# Sheet1.net
KiCad netlist of a schematic drawn in Altium Designer
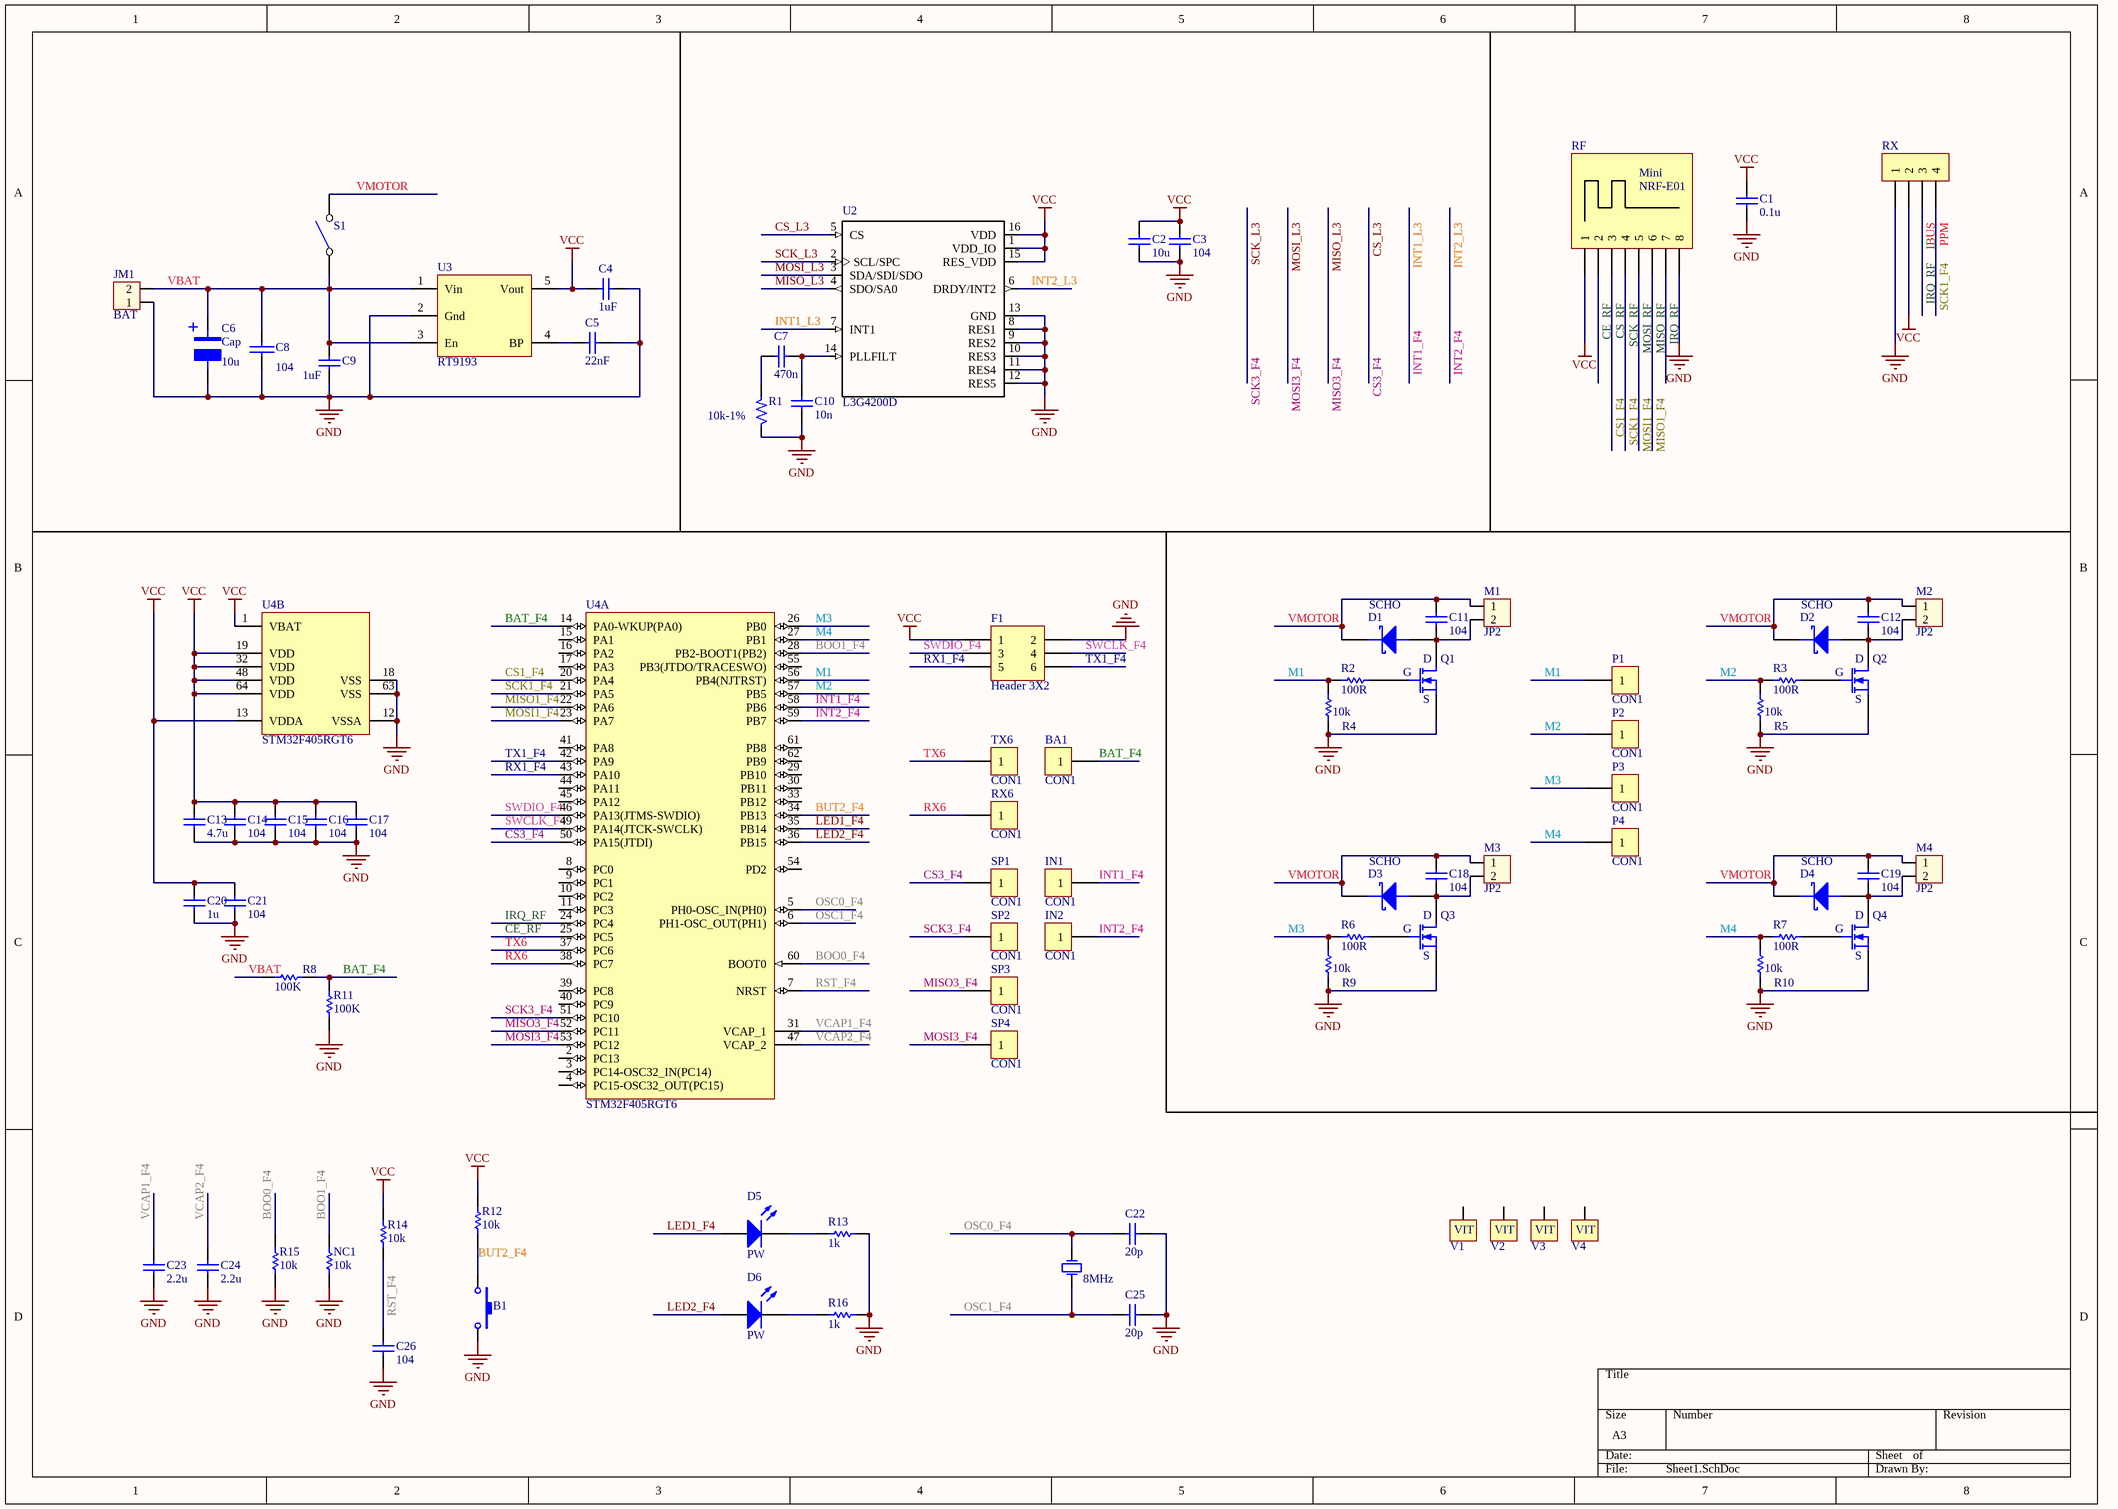
[diagram p0: Sheet1.SchDoc]

(export (version "E")
  (design (tool "Eeschema 10.0.6"))
  (components
    (comp (ref "B1")
      (value "SW-SMD")
      (footprint "SW-SMD")
      (description "Switch")
      (fields (field (name "PUBLISHER") "Altium Limited"))
      (libsource (lib "Cty1") (part "SW-SMD"))
    )
    (comp (ref "BA1")
      (value "CON1")
      (footprint "TEST-POINT")
      (description "Connector")
      (libsource (lib "") (part "CON1_1"))
    )
    (comp (ref "C1")
      (value "0.1u")
      (footprint "Cap-0603")
      (description "Capacitor")
      (fields (field (name "Comment") "Cap") (field (name "PUBLISHER") "Altium Limited"))
      (libsource (lib "Cty1") (part "Cap"))
    )
    (comp (ref "C2")
      (value "10u")
      (footprint "Cap-0603")
      (description "Capacitor")
      (fields (field (name "Comment") "Cap") (field (name "PUBLISHER") "Altium Limited"))
      (libsource (lib "Cty1") (part "Cap"))
    )
    (comp (ref "C3")
      (value "104")
      (footprint "Cap-0603")
      (description "Capacitor")
      (fields (field (name "Comment") "Cap") (field (name "PUBLISHER") "Altium Limited"))
      (libsource (lib "Cty1") (part "Cap"))
    )
    (comp (ref "C4")
      (value "1uF")
      (footprint "Cap-0603")
      (description "Capacitor")
      (fields (field (name "Comment") "Cap") (field (name "PUBLISHER") "Altium Limited"))
      (libsource (lib "Cty1") (part "Cap"))
    )
    (comp (ref "C5")
      (value "22nF")
      (footprint "Cap-0603")
      (description "Capacitor")
      (fields (field (name "Comment") "Cap") (field (name "PUBLISHER") "Altium Limited"))
      (libsource (lib "Cty1") (part "Cap"))
    )
    (comp (ref "C6")
      (value "Cap")
      (footprint "SMT_C_Tantalum_B")
      (fields (field (name "ALTIUM_VALUE") "10u"))
      (libsource (lib "Cty1") (part "Cap Pol"))
    )
    (comp (ref "C7")
      (value "470n")
      (footprint "Cap-0603")
      (description "Capacitor")
      (fields (field (name "Comment") "Cap") (field (name "PUBLISHER") "Altium Limited"))
      (libsource (lib "Cty1") (part "Cap"))
    )
    (comp (ref "C8")
      (value "104")
      (footprint "Cap-0603")
      (description "Capacitor")
      (fields (field (name "Comment") "Cap"))
      (libsource (lib "") (part "Cap_1"))
    )
    (comp (ref "C9")
      (value "1uF")
      (footprint "Cap-0603")
      (description "Capacitor")
      (fields (field (name "Comment") "Cap") (field (name "PUBLISHER") "Altium Limited"))
      (libsource (lib "Cty1") (part "Cap"))
    )
    (comp (ref "C10")
      (value "10n")
      (footprint "Cap-0603")
      (description "Capacitor")
      (fields (field (name "Comment") "Cap") (field (name "PUBLISHER") "Altium Limited"))
      (libsource (lib "Cty1") (part "Cap"))
    )
    (comp (ref "C11")
      (value "104")
      (footprint "Cap-0603")
      (description "Capacitor")
      (fields (field (name "Comment") "Cap") (field (name "PUBLISHER") "Altium Limited"))
      (libsource (lib "Cty1") (part "Cap"))
    )
    (comp (ref "C12")
      (value "104")
      (footprint "Cap-0603")
      (description "Capacitor")
      (fields (field (name "Comment") "Cap") (field (name "PUBLISHER") "Altium Limited"))
      (libsource (lib "Cty1") (part "Cap"))
    )
    (comp (ref "C13")
      (value "4.7u")
      (footprint "Cap-0603")
      (description "Capacitor")
      (fields (field (name "Comment") "Cap") (field (name "PUBLISHER") "Altium Limited"))
      (libsource (lib "Cty1") (part "Cap"))
    )
    (comp (ref "C14")
      (value "104")
      (footprint "Cap-0603")
      (description "Capacitor")
      (fields (field (name "Comment") "Cap") (field (name "PUBLISHER") "Altium Limited"))
      (libsource (lib "Cty1") (part "Cap"))
    )
    (comp (ref "C15")
      (value "104")
      (footprint "Cap-0603")
      (description "Capacitor")
      (fields (field (name "Comment") "Cap") (field (name "PUBLISHER") "Altium Limited"))
      (libsource (lib "Cty1") (part "Cap"))
    )
    (comp (ref "C16")
      (value "104")
      (footprint "Cap-0603")
      (description "Capacitor")
      (fields (field (name "Comment") "Cap") (field (name "PUBLISHER") "Altium Limited"))
      (libsource (lib "Cty1") (part "Cap"))
    )
    (comp (ref "C17")
      (value "104")
      (footprint "Cap-0603")
      (description "Capacitor")
      (fields (field (name "Comment") "Cap") (field (name "PUBLISHER") "Altium Limited"))
      (libsource (lib "Cty1") (part "Cap"))
    )
    (comp (ref "C18")
      (value "104")
      (footprint "Cap-0603")
      (description "Capacitor")
      (fields (field (name "Comment") "Cap") (field (name "PUBLISHER") "Altium Limited"))
      (libsource (lib "Cty1") (part "Cap"))
    )
    (comp (ref "C19")
      (value "104")
      (footprint "Cap-0603")
      (description "Capacitor")
      (fields (field (name "Comment") "Cap") (field (name "PUBLISHER") "Altium Limited"))
      (libsource (lib "Cty1") (part "Cap"))
    )
    (comp (ref "C20")
      (value "1u")
      (footprint "Cap-0603")
      (description "Capacitor")
      (fields (field (name "Comment") "Cap") (field (name "PUBLISHER") "Altium Limited"))
      (libsource (lib "Cty1") (part "Cap"))
    )
    (comp (ref "C21")
      (value "104")
      (footprint "Cap-0603")
      (description "Capacitor")
      (fields (field (name "Comment") "Cap") (field (name "PUBLISHER") "Altium Limited"))
      (libsource (lib "Cty1") (part "Cap"))
    )
    (comp (ref "C22")
      (value "20p")
      (footprint "Cap-0603")
      (description "Capacitor")
      (fields (field (name "Comment") "Cap") (field (name "PUBLISHER") "Altium Limited"))
      (libsource (lib "Cty1") (part "Cap"))
    )
    (comp (ref "C23")
      (value "2.2u")
      (footprint "Cap-0603")
      (description "Capacitor")
      (fields (field (name "Comment") "Cap") (field (name "PUBLISHER") "Altium Limited"))
      (libsource (lib "Cty1") (part "Cap"))
    )
    (comp (ref "C24")
      (value "2.2u")
      (footprint "Cap-0603")
      (description "Capacitor")
      (fields (field (name "Comment") "Cap") (field (name "PUBLISHER") "Altium Limited"))
      (libsource (lib "Cty1") (part "Cap"))
    )
    (comp (ref "C25")
      (value "20p")
      (footprint "Cap-0603")
      (description "Capacitor")
      (fields (field (name "Comment") "Cap") (field (name "PUBLISHER") "Altium Limited"))
      (libsource (lib "Cty1") (part "Cap"))
    )
    (comp (ref "C26")
      (value "104")
      (footprint "Cap-0603")
      (description "Capacitor")
      (fields (field (name "Comment") "Cap") (field (name "PUBLISHER") "Altium Limited"))
      (libsource (lib "Cty1") (part "Cap"))
    )
    (comp (ref "D1")
      (value "SCHO")
      (footprint "SMA")
      (description "Schottky Diode")
      (libsource (lib "Cty1") (part "DIODE SCHOTTKY"))
    )
    (comp (ref "D2")
      (value "SCHO")
      (footprint "SMA")
      (description "Schottky Diode")
      (libsource (lib "Cty1") (part "DIODE SCHOTTKY"))
    )
    (comp (ref "D3")
      (value "SCHO")
      (footprint "SMA")
      (description "Schottky Diode")
      (libsource (lib "Cty1") (part "DIODE SCHOTTKY"))
    )
    (comp (ref "D4")
      (value "SCHO")
      (footprint "SMA")
      (description "Schottky Diode")
      (libsource (lib "Cty1") (part "DIODE SCHOTTKY"))
    )
    (comp (ref "D5")
      (value "PW")
      (footprint "LED_SMD_0805_GREEN")
      (description "Typical INFRARED GaAs LED")
      (fields (field (name "PUBLISHER") "Altium Limited"))
      (libsource (lib "SCH_NHATBON") (part "LED"))
    )
    (comp (ref "D6")
      (value "PW")
      (footprint "LED_SMD_0805_RED")
      (description "Typical INFRARED GaAs LED")
      (fields (field (name "PUBLISHER") "Altium Limited"))
      (libsource (lib "SCH_NHATBON") (part "LED"))
    )
    (comp (ref "F1")
      (value "Header 3X2")
      (footprint "HDR2X3")
      (description "Header, 3-Pin, Dual row")
      (fields (field (name "PUBLISHER") "Altium Limited"))
      (libsource (lib "Cty1") (part "Header 3X2"))
    )
    (comp (ref "IN1")
      (value "CON1")
      (footprint "TEST-POINT")
      (description "Connector")
      (libsource (lib "") (part "CON1_1"))
    )
    (comp (ref "IN2")
      (value "CON1")
      (footprint "TEST-POINT")
      (description "Connector")
      (libsource (lib "") (part "CON1_1"))
    )
    (comp (ref "JM1")
      (value "BAT")
      (footprint "jp2h")
      (description "Connector 2")
      (libsource (lib "Cty1") (part "CON2"))
    )
    (comp (ref "M1")
      (value "JP2")
      (footprint "Con2 - 1.27MM")
      (description "Connector 2")
      (libsource (lib "") (part "CON2_1"))
    )
    (comp (ref "M2")
      (value "JP2")
      (footprint "Con2 - 1.27MM")
      (description "Connector 2")
      (libsource (lib "") (part "CON2_1"))
    )
    (comp (ref "M3")
      (value "JP2")
      (footprint "Con2 - 1.27MM")
      (description "Connector 2")
      (libsource (lib "") (part "CON2_1"))
    )
    (comp (ref "M4")
      (value "JP2")
      (footprint "Con2 - 1.27MM")
      (description "Connector 2")
      (libsource (lib "") (part "CON2_1"))
    )
    (comp (ref "NC1")
      (value "10k")
      (footprint "RES-SMD-0603")
      (description "Semiconductor Resistor")
      (fields (field (name "Comment") "Resistor") (field (name "PUBLISHER") "Altium Limited"))
      (libsource (lib "Cty1") (part "Resistor"))
    )
    (comp (ref "P1")
      (value "CON1")
      (footprint "TEST-POINT")
      (description "Connector")
      (libsource (lib "Cty1") (part "CON1"))
    )
    (comp (ref "P2")
      (value "CON1")
      (footprint "TEST-POINT")
      (description "Connector")
      (libsource (lib "Cty1") (part "CON1"))
    )
    (comp (ref "P3")
      (value "CON1")
      (footprint "TEST-POINT")
      (description "Connector")
      (libsource (lib "Cty1") (part "CON1"))
    )
    (comp (ref "P4")
      (value "CON1")
      (footprint "TEST-POINT")
      (description "Connector")
      (libsource (lib "Cty1") (part "CON1"))
    )
    (comp (ref "Q1")
      (value "Si2302DS")
      (footprint "SOT23-3")
      (description "N-Channel MOSFET")
      (fields (field (name "PUBLISHER") "Altium Limited"))
      (libsource (lib "Cty1") (part "Si2302DS"))
    )
    (comp (ref "Q2")
      (value "Si2302DS")
      (footprint "SOT23-3")
      (description "N-Channel MOSFET")
      (fields (field (name "PUBLISHER") "Altium Limited"))
      (libsource (lib "Cty1") (part "Si2302DS"))
    )
    (comp (ref "Q3")
      (value "Si2302DS")
      (footprint "SOT23-3")
      (description "N-Channel MOSFET")
      (fields (field (name "PUBLISHER") "Altium Limited"))
      (libsource (lib "Cty1") (part "Si2302DS"))
    )
    (comp (ref "Q4")
      (value "Si2302DS")
      (footprint "SOT23-3")
      (description "N-Channel MOSFET")
      (fields (field (name "PUBLISHER") "Altium Limited"))
      (libsource (lib "Cty1") (part "Si2302DS"))
    )
    (comp (ref "R1")
      (value "10k-1%")
      (footprint "RES-SMD-0603")
      (description "Resistor 1/4W")
      (libsource (lib "Cty1") (part "Res"))
    )
    (comp (ref "R2")
      (value "100R")
      (footprint "RES-SMD-0603")
      (description "Semiconductor Resistor")
      (fields (field (name "Comment") "Resistor") (field (name "PUBLISHER") "Altium Limited"))
      (libsource (lib "Cty1") (part "Resistor"))
    )
    (comp (ref "R3")
      (value "100R")
      (footprint "RES-SMD-0603")
      (description "Semiconductor Resistor")
      (fields (field (name "Comment") "Resistor") (field (name "PUBLISHER") "Altium Limited"))
      (libsource (lib "Cty1") (part "Resistor"))
    )
    (comp (ref "R4")
      (value "10k")
      (footprint "RES-SMD-0603")
      (description "Semiconductor Resistor")
      (fields (field (name "Comment") "Resistor") (field (name "PUBLISHER") "Altium Limited"))
      (libsource (lib "Cty1") (part "Resistor"))
    )
    (comp (ref "R5")
      (value "10k")
      (footprint "RES-SMD-0603")
      (description "Semiconductor Resistor")
      (fields (field (name "Comment") "Resistor") (field (name "PUBLISHER") "Altium Limited"))
      (libsource (lib "Cty1") (part "Resistor"))
    )
    (comp (ref "R6")
      (value "100R")
      (footprint "RES-SMD-0603")
      (description "Semiconductor Resistor")
      (fields (field (name "Comment") "Resistor") (field (name "PUBLISHER") "Altium Limited"))
      (libsource (lib "Cty1") (part "Resistor"))
    )
    (comp (ref "R7")
      (value "100R")
      (footprint "RES-SMD-0603")
      (description "Semiconductor Resistor")
      (fields (field (name "Comment") "Resistor") (field (name "PUBLISHER") "Altium Limited"))
      (libsource (lib "Cty1") (part "Resistor"))
    )
    (comp (ref "R8")
      (value "100K")
      (footprint "RES-SMD-0603")
      (description "Semiconductor Resistor")
      (fields (field (name "Comment") "Resistor") (field (name "PUBLISHER") "Altium Limited"))
      (libsource (lib "Cty1") (part "Resistor"))
    )
    (comp (ref "R9")
      (value "10k")
      (footprint "RES-SMD-0603")
      (description "Semiconductor Resistor")
      (fields (field (name "Comment") "Resistor") (field (name "PUBLISHER") "Altium Limited"))
      (libsource (lib "Cty1") (part "Resistor"))
    )
    (comp (ref "R10")
      (value "10k")
      (footprint "RES-SMD-0603")
      (description "Semiconductor Resistor")
      (fields (field (name "Comment") "Resistor") (field (name "PUBLISHER") "Altium Limited"))
      (libsource (lib "Cty1") (part "Resistor"))
    )
    (comp (ref "R11")
      (value "100K")
      (footprint "RES-SMD-0603")
      (description "Semiconductor Resistor")
      (fields (field (name "Comment") "Resistor") (field (name "PUBLISHER") "Altium Limited"))
      (libsource (lib "Cty1") (part "Resistor"))
    )
    (comp (ref "R12")
      (value "10k")
      (footprint "RES-SMD-0603")
      (description "Semiconductor Resistor")
      (fields (field (name "Comment") "Resistor") (field (name "PUBLISHER") "Altium Limited"))
      (libsource (lib "Cty1") (part "Resistor"))
    )
    (comp (ref "R13")
      (value "1k")
      (footprint "RES-SMD-0603")
      (description "Semiconductor Resistor")
      (fields (field (name "Comment") "Resistor") (field (name "PUBLISHER") "Altium Limited"))
      (libsource (lib "Cty1") (part "Resistor"))
    )
    (comp (ref "R14")
      (value "10k")
      (footprint "RES-SMD-0603")
      (description "Semiconductor Resistor")
      (fields (field (name "Comment") "Resistor") (field (name "PUBLISHER") "Altium Limited"))
      (libsource (lib "Cty1") (part "Resistor"))
    )
    (comp (ref "R15")
      (value "10k")
      (footprint "RES-SMD-0603")
      (description "Semiconductor Resistor")
      (fields (field (name "Comment") "Resistor") (field (name "PUBLISHER") "Altium Limited"))
      (libsource (lib "Cty1") (part "Resistor"))
    )
    (comp (ref "R16")
      (value "1k")
      (footprint "RES-SMD-0603")
      (description "Semiconductor Resistor")
      (fields (field (name "Comment") "Resistor") (field (name "PUBLISHER") "Altium Limited"))
      (libsource (lib "Cty1") (part "Resistor"))
    )
    (comp (ref "RF")
      (value "nRF24l01")
      (footprint "NRF-E01")
      (description "nRF24")
      (fields (field (name "PUBLISHER") "Altium Limited"))
      (libsource (lib "Cty1") (part "nRF24"))
    )
    (comp (ref "RX")
      (value "CON4")
      (footprint "SH4-1MM")
      (description "Connector")
      (libsource (lib "Cty1") (part "CON4"))
    )
    (comp (ref "RX6")
      (value "CON1")
      (footprint "TEST-POINT")
      (description "Connector")
      (libsource (lib "Cty1") (part "CON1"))
    )
    (comp (ref "S1") (value "SW SPST") (footprint "SW1-SMD") (libsource (lib "Cty1") (part "SW SPST")))
    (comp (ref "SP1")
      (value "CON1")
      (footprint "TEST-POINT")
      (description "Connector")
      (libsource (lib "Cty1") (part "CON1"))
    )
    (comp (ref "SP2")
      (value "CON1")
      (footprint "TEST-POINT")
      (description "Connector")
      (libsource (lib "Cty1") (part "CON1"))
    )
    (comp (ref "SP3")
      (value "CON1")
      (footprint "TEST-POINT")
      (description "Connector")
      (libsource (lib "Cty1") (part "CON1"))
    )
    (comp (ref "SP4")
      (value "CON1")
      (footprint "TEST-POINT")
      (description "Connector")
      (libsource (lib "Cty1") (part "CON1"))
    )
    (comp (ref "TX6")
      (value "CON1")
      (footprint "TEST-POINT")
      (description "Connector")
      (libsource (lib "Cty1") (part "CON1"))
    )
    (comp (ref "U2")
      (value "L3G4200D")
      (footprint "*PQFN65P400X400X110N")
      (description "Gyroscope X _Pitch_, Y _Roll_, Z _Yaw_ Â±250, 500, 2000 100Hz ~ 800Hz IÂ²C, SPI 16-LGA _4x4_")
      (fields (field (name "MF") "STMicroelectronics"))
      (libsource (lib "Cty1") (part "L3G4200D"))
    )
    (comp (ref "U3") (value "RT9193") (footprint "RT9193") (libsource (lib "Cty1") (part "RT9193")))
    (comp (ref "U4")
      (value "STM32F405RGT6")
      (footprint "STM-LQFP64_N")
      (fields (field (name "MANUFACTURER") "STMicroelectronics"))
      (libsource (lib "STMicroelectronics STM32 F4") (part "STM32F405RGT6"))
    )
    (comp (ref "V1")
      (value "1")
      (footprint "vit-2mm")
      (description "Oc Vit")
      (libsource (lib "Cty1") (part "VIT"))
    )
    (comp (ref "V2")
      (value "1")
      (footprint "vit-2mm")
      (description "Oc Vit")
      (libsource (lib "Cty1") (part "VIT"))
    )
    (comp (ref "V3")
      (value "1")
      (footprint "vit-2mm")
      (description "Oc Vit")
      (libsource (lib "Cty1") (part "VIT"))
    )
    (comp (ref "V4")
      (value "1")
      (footprint "vit-2mm")
      (description "Oc Vit")
      (libsource (lib "Cty1") (part "VIT"))
    )
    (comp (ref "Y1")
      (value "8MHz")
      (footprint "CRY_SMD_5032")
      (description "Crystal Oscillator")
      (fields (field (name "PUBLISHER") "Altium Limited"))
      (libsource (lib "Cty1") (part "Crystal"))
    )
  )
  (nets
    (net (code "1") (name "/BAT_F4") (class "Default")
      (node (ref "BA1") (pin "1") (pinfunction "1_1") (pintype "passive"))
      (node (ref "R11") (pin "2") (pinfunction "2_2") (pintype "passive"))
      (node (ref "R8") (pin "2") (pinfunction "2_2") (pintype "passive"))
      (node (ref "U4") (pin "14") (pinfunction "PA0-WKUP(PA0)_14") (pintype "bidirectional"))
    )
    (net (code "2") (name "/BOO0_F4") (class "Default")
      (node (ref "R15") (pin "2") (pinfunction "2_2") (pintype "passive"))
      (node (ref "U4") (pin "60") (pinfunction "BOOT0_60") (pintype "input"))
    )
    (net (code "3") (name "/BOO1_F4") (class "Default")
      (node (ref "NC1") (pin "2") (pinfunction "2_2") (pintype "passive"))
      (node (ref "U4") (pin "28") (pinfunction "PB2-BOOT1(PB2)_28") (pintype "bidirectional"))
    )
    (net (code "4") (name "/BUT2_F4") (class "Default")
      (node (ref "B1") (pin "1") (pinfunction "1_1") (pintype "passive"))
      (node (ref "R12") (pin "1") (pinfunction "1_1") (pintype "passive"))
      (node (ref "U4") (pin "34") (pinfunction "PB13_34") (pintype "bidirectional"))
    )
    (net (code "5") (name "/CE_RF") (class "Default")
      (node (ref "RF") (pin "2") (pinfunction "2_2") (pintype "passive"))
      (node (ref "U4") (pin "25") (pinfunction "PC5_25") (pintype "bidirectional"))
    )
    (net (code "6") (name "/CS1_F4") (class "Default")
      (node (ref "RF") (pin "3") (pinfunction "3_3") (pintype "passive"))
      (node (ref "U4") (pin "20") (pinfunction "PA4_20") (pintype "bidirectional"))
    )
    (net (code "7") (name "/CS3_F4") (class "Default")
      (node (ref "SP1") (pin "1") (pinfunction "1_1") (pintype "passive"))
      (node (ref "U2") (pin "5") (pinfunction "CS_5") (pintype "input"))
      (node (ref "U4") (pin "50") (pinfunction "PA15(JTDI)_50") (pintype "bidirectional"))
    )
    (net (code "8") (name "/IBUS") (class "Default")
      (node (ref "RF") (pin "7") (pinfunction "7_7") (pintype "passive"))
      (node (ref "RX") (pin "3") (pinfunction "3_3") (pintype "passive"))
      (node (ref "U4") (pin "24") (pinfunction "PC4_24") (pintype "bidirectional"))
    )
    (net (code "9") (name "/INT1_F4") (class "Default")
      (node (ref "IN1") (pin "1") (pinfunction "1_1") (pintype "passive"))
      (node (ref "U2") (pin "7") (pinfunction "INT1_7") (pintype "input"))
      (node (ref "U4") (pin "58") (pinfunction "PB6_58") (pintype "bidirectional"))
    )
    (net (code "10") (name "/INT2_F4") (class "Default")
      (node (ref "IN2") (pin "1") (pinfunction "1_1") (pintype "passive"))
      (node (ref "U2") (pin "6") (pinfunction "DRDY/INT2_6") (pintype "output"))
      (node (ref "U4") (pin "59") (pinfunction "PB7_59") (pintype "bidirectional"))
    )
    (net (code "11") (name "/LED1_F4") (class "Default")
      (node (ref "D5") (pin "1") (pinfunction "A_1") (pintype "passive"))
      (node (ref "U4") (pin "35") (pinfunction "PB14_35") (pintype "bidirectional"))
    )
    (net (code "12") (name "/LED2_F4") (class "Default")
      (node (ref "D6") (pin "1") (pinfunction "A_1") (pintype "passive"))
      (node (ref "U4") (pin "36") (pinfunction "PB15_36") (pintype "bidirectional"))
    )
    (net (code "13") (name "/M1") (class "Default")
      (node (ref "P1") (pin "1") (pinfunction "1_1") (pintype "passive"))
      (node (ref "R2") (pin "2") (pinfunction "2_2") (pintype "passive"))
      (node (ref "R4") (pin "1") (pinfunction "1_1") (pintype "passive"))
      (node (ref "U4") (pin "56") (pinfunction "PB4(NJTRST)_56") (pintype "bidirectional"))
    )
    (net (code "14") (name "/M2") (class "Default")
      (node (ref "P2") (pin "1") (pinfunction "1_1") (pintype "passive"))
      (node (ref "R3") (pin "2") (pinfunction "2_2") (pintype "passive"))
      (node (ref "R5") (pin "1") (pinfunction "1_1") (pintype "passive"))
      (node (ref "U4") (pin "57") (pinfunction "PB5_57") (pintype "bidirectional"))
    )
    (net (code "15") (name "/M3") (class "Default")
      (node (ref "P3") (pin "1") (pinfunction "1_1") (pintype "passive"))
      (node (ref "R6") (pin "2") (pinfunction "2_2") (pintype "passive"))
      (node (ref "R9") (pin "1") (pinfunction "1_1") (pintype "passive"))
      (node (ref "U4") (pin "26") (pinfunction "PB0_26") (pintype "bidirectional"))
    )
    (net (code "16") (name "/M4") (class "Default")
      (node (ref "P4") (pin "1") (pinfunction "1_1") (pintype "passive"))
      (node (ref "R10") (pin "1") (pinfunction "1_1") (pintype "passive"))
      (node (ref "R7") (pin "2") (pinfunction "2_2") (pintype "passive"))
      (node (ref "U4") (pin "27") (pinfunction "PB1_27") (pintype "bidirectional"))
    )
    (net (code "17") (name "/MISO1_F4") (class "Default")
      (node (ref "RF") (pin "6") (pinfunction "6_6") (pintype "passive"))
      (node (ref "U4") (pin "22") (pinfunction "PA6_22") (pintype "bidirectional"))
    )
    (net (code "18") (name "/MISO3_F4") (class "Default")
      (node (ref "SP3") (pin "1") (pinfunction "1_1") (pintype "passive"))
      (node (ref "U2") (pin "4") (pinfunction "SDO/SA0_4") (pintype "output"))
      (node (ref "U4") (pin "52") (pinfunction "PC11_52") (pintype "bidirectional"))
    )
    (net (code "19") (name "/MOSI1_F4") (class "Default")
      (node (ref "RF") (pin "5") (pinfunction "5_5") (pintype "passive"))
      (node (ref "U4") (pin "23") (pinfunction "PA7_23") (pintype "bidirectional"))
    )
    (net (code "20") (name "/MOSI3_F4") (class "Default")
      (node (ref "SP4") (pin "1") (pinfunction "1_1") (pintype "passive"))
      (node (ref "U2") (pin "3") (pinfunction "SDA/SDI/SDO_3") (pintype "bidirectional"))
      (node (ref "U4") (pin "53") (pinfunction "PC12_53") (pintype "bidirectional"))
    )
    (net (code "21") (name "/OSC0_F4") (class "Default")
      (node (ref "C22") (pin "2") (pinfunction "2_2") (pintype "passive"))
      (node (ref "U4") (pin "5") (pinfunction "PH0-OSC_IN(PH0)_5") (pintype "bidirectional"))
      (node (ref "Y1") (pin "2") (pinfunction "OSC2_2") (pintype "passive"))
    )
    (net (code "22") (name "/OSC1_F4") (class "Default")
      (node (ref "C25") (pin "2") (pinfunction "2_2") (pintype "passive"))
      (node (ref "U4") (pin "6") (pinfunction "PH1-OSC_OUT(PH1)_6") (pintype "bidirectional"))
      (node (ref "Y1") (pin "1") (pinfunction "OSC1_1") (pintype "passive"))
    )
    (net (code "23") (name "/PPM") (class "Default")
      (node (ref "RF") (pin "4") (pinfunction "4_4") (pintype "passive"))
      (node (ref "RX") (pin "4") (pinfunction "4_4") (pintype "passive"))
      (node (ref "U4") (pin "21") (pinfunction "PA5_21") (pintype "bidirectional"))
    )
    (net (code "24") (name "/RST_F4") (class "Default")
      (node (ref "C26") (pin "2") (pinfunction "2_2") (pintype "passive"))
      (node (ref "R14") (pin "1") (pinfunction "1_1") (pintype "passive"))
      (node (ref "U4") (pin "7") (pinfunction "NRST_7") (pintype "bidirectional"))
    )
    (net (code "25") (name "/RX1_F4") (class "Default")
      (node (ref "F1") (pin "5") (pinfunction "5_5") (pintype "passive"))
      (node (ref "U4") (pin "43") (pinfunction "PA10_43") (pintype "bidirectional"))
    )
    (net (code "26") (name "/RX6") (class "Default")
      (node (ref "RX6") (pin "1") (pinfunction "1_1") (pintype "passive"))
      (node (ref "U4") (pin "38") (pinfunction "PC7_38") (pintype "bidirectional"))
    )
    (net (code "27") (name "/SCK3_F4") (class "Default")
      (node (ref "SP2") (pin "1") (pinfunction "1_1") (pintype "passive"))
      (node (ref "U2") (pin "2") (pinfunction "SCL/SPC_2") (pintype "input"))
      (node (ref "U4") (pin "51") (pinfunction "PC10_51") (pintype "bidirectional"))
    )
    (net (code "28") (name "/SWCLK_F4") (class "Default")
      (node (ref "F1") (pin "4") (pinfunction "4_4") (pintype "passive"))
      (node (ref "U4") (pin "49") (pinfunction "PA14(JTCK-SWCLK)_49") (pintype "bidirectional"))
    )
    (net (code "29") (name "/SWDIO_F4") (class "Default")
      (node (ref "F1") (pin "3") (pinfunction "3_3") (pintype "passive"))
      (node (ref "U4") (pin "46") (pinfunction "PA13(JTMS-SWDIO)_46") (pintype "bidirectional"))
    )
    (net (code "30") (name "/TX1_F4") (class "Default")
      (node (ref "F1") (pin "6") (pinfunction "6_6") (pintype "passive"))
      (node (ref "U4") (pin "42") (pinfunction "PA9_42") (pintype "bidirectional"))
    )
    (net (code "31") (name "/TX6") (class "Default")
      (node (ref "TX6") (pin "1") (pinfunction "1_1") (pintype "passive"))
      (node (ref "U4") (pin "37") (pinfunction "PC6_37") (pintype "bidirectional"))
    )
    (net (code "32") (name "/VBAT") (class "Default")
      (node (ref "C6") (pin "1") (pinfunction "1_1") (pintype "passive"))
      (node (ref "C8") (pin "1") (pinfunction "1_1") (pintype "passive"))
      (node (ref "C9") (pin "1") (pinfunction "1_1") (pintype "passive"))
      (node (ref "JM1") (pin "2") (pinfunction "2_2") (pintype "passive"))
      (node (ref "R8") (pin "1") (pinfunction "1_1") (pintype "passive"))
      (node (ref "S1") (pin "1") (pinfunction "COMMON_1") (pintype "passive"))
      (node (ref "U3") (pin "1") (pinfunction "Vin_1") (pintype "passive"))
      (node (ref "U3") (pin "3") (pinfunction "En_3") (pintype "passive"))
    )
    (net (code "33") (name "/VCAP1_F4") (class "Default")
      (node (ref "C23") (pin "2") (pinfunction "2_2") (pintype "passive"))
      (node (ref "U4") (pin "31") (pinfunction "VCAP_1_31") (pintype "power_in"))
    )
    (net (code "34") (name "/VCAP2_F4") (class "Default")
      (node (ref "C24") (pin "2") (pinfunction "2_2") (pintype "passive"))
      (node (ref "U4") (pin "47") (pinfunction "VCAP_2_47") (pintype "power_in"))
    )
    (net (code "35") (name "/VMOTOR") (class "Default")
      (node (ref "C11") (pin "2") (pinfunction "2_2") (pintype "passive"))
      (node (ref "C12") (pin "2") (pinfunction "2_2") (pintype "passive"))
      (node (ref "C18") (pin "2") (pinfunction "2_2") (pintype "passive"))
      (node (ref "C19") (pin "2") (pinfunction "2_2") (pintype "passive"))
      (node (ref "D1") (pin "2") (pinfunction "K_2") (pintype "passive"))
      (node (ref "D2") (pin "2") (pinfunction "K_2") (pintype "passive"))
      (node (ref "D3") (pin "2") (pinfunction "K_2") (pintype "passive"))
      (node (ref "D4") (pin "2") (pinfunction "K_2") (pintype "passive"))
      (node (ref "M1") (pin "1") (pinfunction "1_1") (pintype "passive"))
      (node (ref "M2") (pin "1") (pinfunction "1_1") (pintype "passive"))
      (node (ref "M3") (pin "1") (pinfunction "1_1") (pintype "passive"))
      (node (ref "M4") (pin "1") (pinfunction "1_1") (pintype "passive"))
      (node (ref "S1") (pin "2") (pinfunction "NO_2") (pintype "passive"))
    )
    (net (code "36") (name "GND") (class "Default")
      (node (ref "B1") (pin "2") (pinfunction "2_2") (pintype "passive"))
      (node (ref "C1") (pin "1") (pinfunction "1_1") (pintype "passive"))
      (node (ref "C10") (pin "1") (pinfunction "1_1") (pintype "passive"))
      (node (ref "C13") (pin "1") (pinfunction "1_1") (pintype "passive"))
      (node (ref "C14") (pin "1") (pinfunction "1_1") (pintype "passive"))
      (node (ref "C15") (pin "1") (pinfunction "1_1") (pintype "passive"))
      (node (ref "C16") (pin "1") (pinfunction "1_1") (pintype "passive"))
      (node (ref "C17") (pin "1") (pinfunction "1_1") (pintype "passive"))
      (node (ref "C2") (pin "1") (pinfunction "1_1") (pintype "passive"))
      (node (ref "C20") (pin "1") (pinfunction "1_1") (pintype "passive"))
      (node (ref "C21") (pin "1") (pinfunction "1_1") (pintype "passive"))
      (node (ref "C22") (pin "1") (pinfunction "1_1") (pintype "passive"))
      (node (ref "C23") (pin "1") (pinfunction "1_1") (pintype "passive"))
      (node (ref "C24") (pin "1") (pinfunction "1_1") (pintype "passive"))
      (node (ref "C25") (pin "1") (pinfunction "1_1") (pintype "passive"))
      (node (ref "C26") (pin "1") (pinfunction "1_1") (pintype "passive"))
      (node (ref "C3") (pin "1") (pinfunction "1_1") (pintype "passive"))
      (node (ref "C4") (pin "1") (pinfunction "1_1") (pintype "passive"))
      (node (ref "C5") (pin "1") (pinfunction "1_1") (pintype "passive"))
      (node (ref "C6") (pin "2") (pinfunction "2_2") (pintype "passive"))
      (node (ref "C8") (pin "2") (pinfunction "2_2") (pintype "passive"))
      (node (ref "C9") (pin "2") (pinfunction "2_2") (pintype "passive"))
      (node (ref "F1") (pin "2") (pinfunction "2_2") (pintype "passive"))
      (node (ref "JM1") (pin "1") (pinfunction "1_1") (pintype "passive"))
      (node (ref "NC1") (pin "1") (pinfunction "1_1") (pintype "passive"))
      (node (ref "Q1") (pin "2") (pinfunction "S_2") (pintype "passive"))
      (node (ref "Q2") (pin "2") (pinfunction "S_2") (pintype "passive"))
      (node (ref "Q3") (pin "2") (pinfunction "S_2") (pintype "passive"))
      (node (ref "Q4") (pin "2") (pinfunction "S_2") (pintype "passive"))
      (node (ref "R1") (pin "1") (pinfunction "1_1") (pintype "passive"))
      (node (ref "R10") (pin "2") (pinfunction "2_2") (pintype "passive"))
      (node (ref "R11") (pin "1") (pinfunction "1_1") (pintype "passive"))
      (node (ref "R13") (pin "2") (pinfunction "2_2") (pintype "passive"))
      (node (ref "R15") (pin "1") (pinfunction "1_1") (pintype "passive"))
      (node (ref "R16") (pin "2") (pinfunction "2_2") (pintype "passive"))
      (node (ref "R4") (pin "2") (pinfunction "2_2") (pintype "passive"))
      (node (ref "R5") (pin "2") (pinfunction "2_2") (pintype "passive"))
      (node (ref "R9") (pin "2") (pinfunction "2_2") (pintype "passive"))
      (node (ref "RF") (pin "8") (pinfunction "8_8") (pintype "passive"))
      (node (ref "RX") (pin "1") (pinfunction "1_1") (pintype "passive"))
      (node (ref "U2") (pin "10") (pinfunction "RES3_10") (pintype "power_in"))
      (node (ref "U2") (pin "11") (pinfunction "RES4_11") (pintype "power_in"))
      (node (ref "U2") (pin "12") (pinfunction "RES5_12") (pintype "power_in"))
      (node (ref "U2") (pin "13") (pinfunction "GND_13") (pintype "power_in"))
      (node (ref "U2") (pin "8") (pinfunction "RES1_8") (pintype "power_in"))
      (node (ref "U2") (pin "9") (pinfunction "RES2_9") (pintype "power_in"))
      (node (ref "U3") (pin "2") (pinfunction "Gnd_2") (pintype "passive"))
      (node (ref "U4") (pin "12") (pinfunction "VSSA_12") (pintype "power_in"))
      (node (ref "U4") (pin "18") (pinfunction "VSS_18") (pintype "power_in"))
      (node (ref "U4") (pin "63") (pinfunction "VSS_63") (pintype "power_in"))
    )
    (net (code "37") (name "Net-(C7-Pad1)") (class "Default")
      (node (ref "C7") (pin "1") (pinfunction "1_1") (pintype "passive"))
      (node (ref "R1") (pin "2") (pinfunction "2_2") (pintype "passive"))
    )
    (net (code "38") (name "Net-(D1-A)") (class "Default")
      (node (ref "C11") (pin "1") (pinfunction "1_1") (pintype "passive"))
      (node (ref "D1") (pin "1") (pinfunction "A_1") (pintype "passive"))
      (node (ref "M1") (pin "2") (pinfunction "2_2") (pintype "passive"))
      (node (ref "Q1") (pin "3") (pinfunction "D_3") (pintype "passive"))
    )
    (net (code "39") (name "Net-(D2-A)") (class "Default")
      (node (ref "C12") (pin "1") (pinfunction "1_1") (pintype "passive"))
      (node (ref "D2") (pin "1") (pinfunction "A_1") (pintype "passive"))
      (node (ref "M2") (pin "2") (pinfunction "2_2") (pintype "passive"))
      (node (ref "Q2") (pin "3") (pinfunction "D_3") (pintype "passive"))
    )
    (net (code "40") (name "Net-(D3-A)") (class "Default")
      (node (ref "C18") (pin "1") (pinfunction "1_1") (pintype "passive"))
      (node (ref "D3") (pin "1") (pinfunction "A_1") (pintype "passive"))
      (node (ref "M3") (pin "2") (pinfunction "2_2") (pintype "passive"))
      (node (ref "Q3") (pin "3") (pinfunction "D_3") (pintype "passive"))
    )
    (net (code "41") (name "Net-(D4-A)") (class "Default")
      (node (ref "C19") (pin "1") (pinfunction "1_1") (pintype "passive"))
      (node (ref "D4") (pin "1") (pinfunction "A_1") (pintype "passive"))
      (node (ref "M4") (pin "2") (pinfunction "2_2") (pintype "passive"))
      (node (ref "Q4") (pin "3") (pinfunction "D_3") (pintype "passive"))
    )
    (net (code "42") (name "Net-(D5-K)") (class "Default")
      (node (ref "D5") (pin "2") (pinfunction "K_2") (pintype "passive"))
      (node (ref "R13") (pin "1") (pinfunction "1_1") (pintype "passive"))
    )
    (net (code "43") (name "Net-(D6-K)") (class "Default")
      (node (ref "D6") (pin "2") (pinfunction "K_2") (pintype "passive"))
      (node (ref "R16") (pin "1") (pinfunction "1_1") (pintype "passive"))
    )
    (net (code "44") (name "Net-(Q1-G)") (class "Default")
      (node (ref "Q1") (pin "1") (pinfunction "G_1") (pintype "passive"))
      (node (ref "R2") (pin "1") (pinfunction "1_1") (pintype "passive"))
    )
    (net (code "45") (name "Net-(Q2-G)") (class "Default")
      (node (ref "Q2") (pin "1") (pinfunction "G_1") (pintype "passive"))
      (node (ref "R3") (pin "1") (pinfunction "1_1") (pintype "passive"))
    )
    (net (code "46") (name "Net-(Q3-G)") (class "Default")
      (node (ref "Q3") (pin "1") (pinfunction "G_1") (pintype "passive"))
      (node (ref "R6") (pin "1") (pinfunction "1_1") (pintype "passive"))
    )
    (net (code "47") (name "Net-(Q4-G)") (class "Default")
      (node (ref "Q4") (pin "1") (pinfunction "G_1") (pintype "passive"))
      (node (ref "R7") (pin "1") (pinfunction "1_1") (pintype "passive"))
    )
    (net (code "48") (name "Net-(U2-PLLFILT)") (class "Default")
      (node (ref "C10") (pin "2") (pinfunction "2_2") (pintype "passive"))
      (node (ref "C7") (pin "2") (pinfunction "2_2") (pintype "passive"))
      (node (ref "U2") (pin "14") (pinfunction "PLLFILT_14") (pintype "input"))
    )
    (net (code "49") (name "Net-(U3-BP)") (class "Default")
      (node (ref "C5") (pin "2") (pinfunction "2_2") (pintype "passive"))
      (node (ref "U3") (pin "4") (pinfunction "BP_4") (pintype "passive"))
    )
    (net (code "50") (name "VCC") (class "Default")
      (node (ref "C1") (pin "2") (pinfunction "2_2") (pintype "passive"))
      (node (ref "C13") (pin "2") (pinfunction "2_2") (pintype "passive"))
      (node (ref "C14") (pin "2") (pinfunction "2_2") (pintype "passive"))
      (node (ref "C15") (pin "2") (pinfunction "2_2") (pintype "passive"))
      (node (ref "C16") (pin "2") (pinfunction "2_2") (pintype "passive"))
      (node (ref "C17") (pin "2") (pinfunction "2_2") (pintype "passive"))
      (node (ref "C2") (pin "2") (pinfunction "2_2") (pintype "passive"))
      (node (ref "C20") (pin "2") (pinfunction "2_2") (pintype "passive"))
      (node (ref "C21") (pin "2") (pinfunction "2_2") (pintype "passive"))
      (node (ref "C3") (pin "2") (pinfunction "2_2") (pintype "passive"))
      (node (ref "C4") (pin "2") (pinfunction "2_2") (pintype "passive"))
      (node (ref "F1") (pin "1") (pinfunction "1_1") (pintype "passive"))
      (node (ref "R12") (pin "2") (pinfunction "2_2") (pintype "passive"))
      (node (ref "R14") (pin "2") (pinfunction "2_2") (pintype "passive"))
      (node (ref "RF") (pin "1") (pinfunction "1_1") (pintype "passive"))
      (node (ref "RX") (pin "2") (pinfunction "2_2") (pintype "passive"))
      (node (ref "U2") (pin "1") (pinfunction "VDD_IO_1") (pintype "power_in"))
      (node (ref "U2") (pin "15") (pinfunction "RES_VDD_15") (pintype "power_in"))
      (node (ref "U2") (pin "16") (pinfunction "VDD_16") (pintype "power_in"))
      (node (ref "U3") (pin "5") (pinfunction "Vout_5") (pintype "passive"))
      (node (ref "U4") (pin "1") (pinfunction "VBAT_1") (pintype "power_in"))
      (node (ref "U4") (pin "13") (pinfunction "VDDA_13") (pintype "power_in"))
      (node (ref "U4") (pin "19") (pinfunction "VDD_19") (pintype "power_in"))
      (node (ref "U4") (pin "32") (pinfunction "VDD_32") (pintype "power_in"))
      (node (ref "U4") (pin "48") (pinfunction "VDD_48") (pintype "power_in"))
      (node (ref "U4") (pin "64") (pinfunction "VDD_64") (pintype "power_in"))
    )
    (net (code "51") (name "unconnected-(U4A-PA1-Pad15)") (class "Default")
      (node (ref "U4") (pin "15") (pinfunction "PA1_15") (pintype "bidirectional"))
    )
    (net (code "52") (name "unconnected-(U4A-PA2-Pad16)") (class "Default")
      (node (ref "U4") (pin "16") (pinfunction "PA2_16") (pintype "bidirectional"))
    )
    (net (code "53") (name "unconnected-(U4A-PA3-Pad17)") (class "Default")
      (node (ref "U4") (pin "17") (pinfunction "PA3_17") (pintype "bidirectional"))
    )
    (net (code "54") (name "unconnected-(U4A-PA8-Pad41)") (class "Default")
      (node (ref "U4") (pin "41") (pinfunction "PA8_41") (pintype "bidirectional"))
    )
    (net (code "55") (name "unconnected-(U4A-PA11-Pad44)") (class "Default")
      (node (ref "U4") (pin "44") (pinfunction "PA11_44") (pintype "bidirectional"))
    )
    (net (code "56") (name "unconnected-(U4A-PA12-Pad45)") (class "Default")
      (node (ref "U4") (pin "45") (pinfunction "PA12_45") (pintype "bidirectional"))
    )
    (net (code "57") (name "unconnected-(U4A-PB3(JTDO{slash}TRACESWO)-Pad55)") (class "Default")
      (node (ref "U4") (pin "55") (pinfunction "PB3(JTDO/TRACESWO)_55") (pintype "bidirectional"))
    )
    (net (code "58") (name "unconnected-(U4A-PB8-Pad61)") (class "Default")
      (node (ref "U4") (pin "61") (pinfunction "PB8_61") (pintype "bidirectional"))
    )
    (net (code "59") (name "unconnected-(U4A-PB9-Pad62)") (class "Default")
      (node (ref "U4") (pin "62") (pinfunction "PB9_62") (pintype "bidirectional"))
    )
    (net (code "60") (name "unconnected-(U4A-PB10-Pad29)") (class "Default")
      (node (ref "U4") (pin "29") (pinfunction "PB10_29") (pintype "bidirectional"))
    )
    (net (code "61") (name "unconnected-(U4A-PB11-Pad30)") (class "Default")
      (node (ref "U4") (pin "30") (pinfunction "PB11_30") (pintype "bidirectional"))
    )
    (net (code "62") (name "unconnected-(U4A-PB12-Pad33)") (class "Default")
      (node (ref "U4") (pin "33") (pinfunction "PB12_33") (pintype "bidirectional"))
    )
    (net (code "63") (name "unconnected-(U4A-PC0-Pad8)") (class "Default")
      (node (ref "U4") (pin "8") (pinfunction "PC0_8") (pintype "bidirectional"))
    )
    (net (code "64") (name "unconnected-(U4A-PC1-Pad9)") (class "Default")
      (node (ref "U4") (pin "9") (pinfunction "PC1_9") (pintype "bidirectional"))
    )
    (net (code "65") (name "unconnected-(U4A-PC2-Pad10)") (class "Default")
      (node (ref "U4") (pin "10") (pinfunction "PC2_10") (pintype "bidirectional"))
    )
    (net (code "66") (name "unconnected-(U4A-PC3-Pad11)") (class "Default")
      (node (ref "U4") (pin "11") (pinfunction "PC3_11") (pintype "bidirectional"))
    )
    (net (code "67") (name "unconnected-(U4A-PC8-Pad39)") (class "Default")
      (node (ref "U4") (pin "39") (pinfunction "PC8_39") (pintype "bidirectional"))
    )
    (net (code "68") (name "unconnected-(U4A-PC9-Pad40)") (class "Default")
      (node (ref "U4") (pin "40") (pinfunction "PC9_40") (pintype "bidirectional"))
    )
    (net (code "69") (name "unconnected-(U4A-PC13-Pad2)") (class "Default")
      (node (ref "U4") (pin "2") (pinfunction "PC13_2") (pintype "bidirectional"))
    )
    (net (code "70") (name "unconnected-(U4A-PC14-OSC32_IN(PC14)-Pad3)") (class "Default")
      (node (ref "U4") (pin "3") (pinfunction "PC14-OSC32_IN(PC14)_3") (pintype "bidirectional"))
    )
    (net (code "71") (name "unconnected-(U4A-PC15-OSC32_OUT(PC15)-Pad4)") (class "Default")
      (node (ref "U4") (pin "4") (pinfunction "PC15-OSC32_OUT(PC15)_4") (pintype "bidirectional"))
    )
    (net (code "72") (name "unconnected-(U4A-PD2-Pad54)") (class "Default")
      (node (ref "U4") (pin "54") (pinfunction "PD2_54") (pintype "bidirectional"))
    )
    (net (code "73") (name "unconnected-(V1-1-PadVIT1)") (class "Default")
      (node (ref "V1") (pin "VIT1") (pinfunction "1_VIT1") (pintype "passive"))
    )
    (net (code "74") (name "unconnected-(V2-1-PadVIT1)") (class "Default")
      (node (ref "V2") (pin "VIT1") (pinfunction "1_VIT1") (pintype "passive"))
    )
    (net (code "75") (name "unconnected-(V3-1-PadVIT1)") (class "Default")
      (node (ref "V3") (pin "VIT1") (pinfunction "1_VIT1") (pintype "passive"))
    )
    (net (code "76") (name "unconnected-(V4-1-PadVIT1)") (class "Default")
      (node (ref "V4") (pin "VIT1") (pinfunction "1_VIT1") (pintype "passive"))
    )
  )
)
